# smartswitch.net
KiCad netlist of a schematic drawn in EAGLE
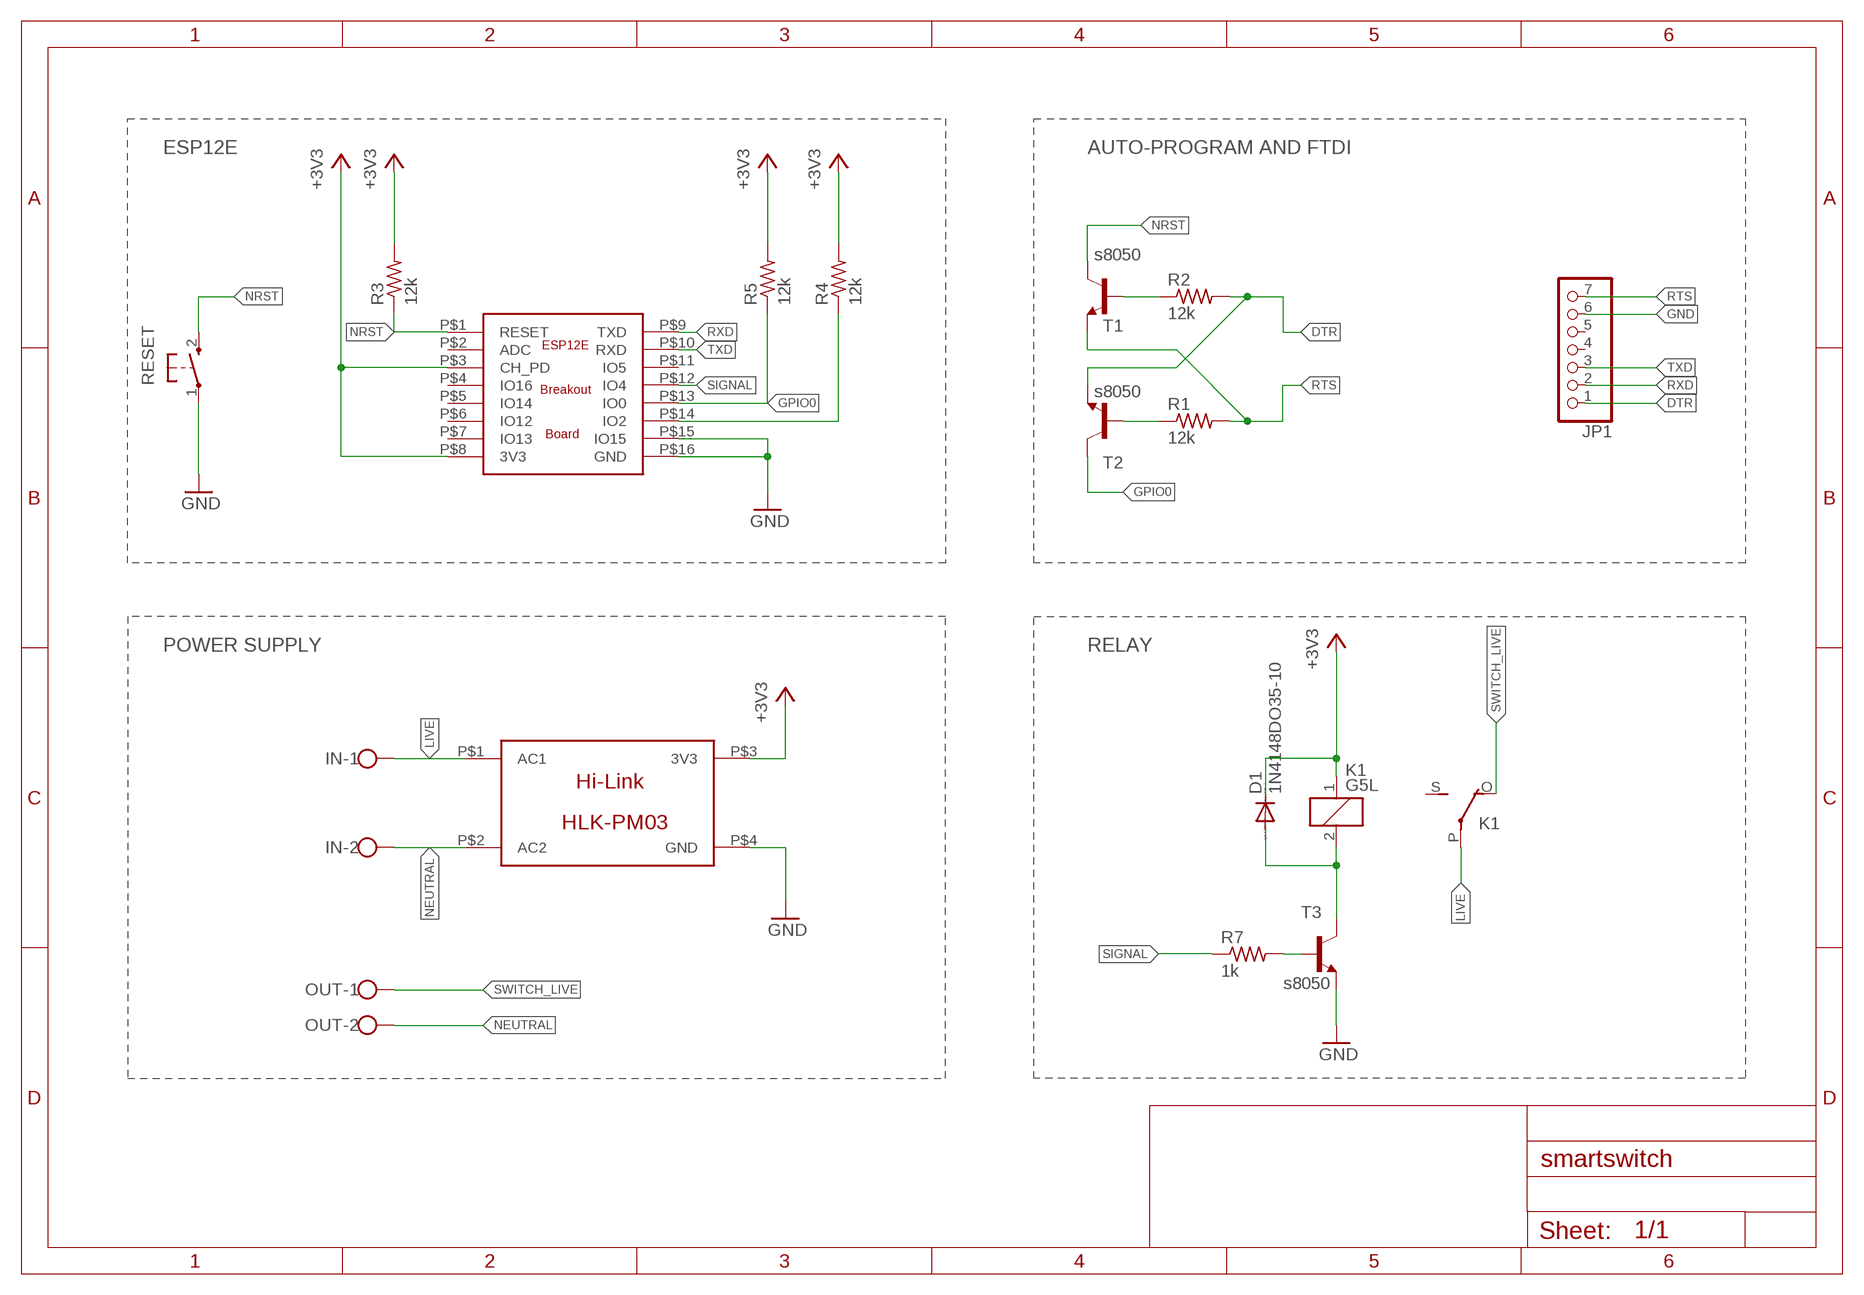
[diagram p0: schematic, sheet 1]

(export (version "E")
  (design (tool "Eeschema 10.0.6"))
  (components
    (comp (ref "D1")
      (value "1N4148DO35-10")
      (footprint "eagle-import:DO35-10")
      (libsource (lib "eagle-import") (part "1N4148DO35-10"))
    )
    (comp (ref "IN")
      (value "W237-102")
      (footprint "eagle-import:W237-102")
      (fields (field (name "MPN") "237-102"))
      (libsource (lib "eagle-import") (part "W237-102"))
    )
    (comp (ref "JP1")
      (value "PINHD-1X7")
      (footprint "eagle-import:1X07")
      (libsource (lib "eagle-import") (part "PINHD-1X7"))
    )
    (comp (ref "K1")
      (value "G5L")
      (footprint "eagle-import:G5LE")
      (libsource (lib "eagle-import") (part "G5L"))
    )
    (comp (ref "OUT")
      (value "W237-102")
      (footprint "eagle-import:W237-102")
      (fields (field (name "MPN") "237-102"))
      (libsource (lib "eagle-import") (part "W237-102"))
    )
    (comp (ref "R1")
      (value "12k")
      (footprint "eagle-import:0309_12")
      (libsource (lib "eagle-import") (part "R-US_0309/12"))
    )
    (comp (ref "R2")
      (value "12k")
      (footprint "eagle-import:0309_12")
      (libsource (lib "eagle-import") (part "R-US_0309/12"))
    )
    (comp (ref "R3")
      (value "12k")
      (footprint "eagle-import:0309_12")
      (libsource (lib "eagle-import") (part "R-US_0309/12"))
    )
    (comp (ref "R4")
      (value "12k")
      (footprint "eagle-import:0309_12")
      (libsource (lib "eagle-import") (part "R-US_0309/12"))
    )
    (comp (ref "R5")
      (value "12k")
      (footprint "eagle-import:0309_12")
      (libsource (lib "eagle-import") (part "R-US_0309/12"))
    )
    (comp (ref "R7")
      (value "1k")
      (footprint "eagle-import:0309_12")
      (libsource (lib "eagle-import") (part "R-US_0309/12"))
    )
    (comp (ref "RESET")
      (value "PB")
      (footprint "eagle-import:PBTH")
      (libsource (lib "eagle-import") (part "PB"))
    )
    (comp (ref "T1")
      (value "s8050")
      (footprint "eagle-import:TO92-EBC")
      (libsource (lib "eagle-import") (part "-NPN-TO92-EBC"))
    )
    (comp (ref "T2")
      (value "s8050")
      (footprint "eagle-import:TO92-EBC")
      (libsource (lib "eagle-import") (part "-NPN-TO92-EBC"))
    )
    (comp (ref "T3")
      (value "s8050")
      (footprint "eagle-import:TO92-EBC")
      (libsource (lib "eagle-import") (part "-NPN-TO92-EBC"))
    )
    (comp (ref "U$1")
      (value "ESP12E_BREAKOUT")
      (footprint "eagle-import:ESP12E")
      (libsource (lib "eagle-import") (part "ESP12E_BREAKOUT"))
    )
    (comp (ref "U$2")
      (value "HLK-PM03")
      (footprint "eagle-import:HLK-PM03")
      (libsource (lib "eagle-import") (part "HLK-PM03"))
    )
  )
  (nets
    (net (code "1") (name "+3V3") (class "Default")
      (node (ref "D1") (pin "C") (pinfunction "C_C") (pintype "passive"))
      (node (ref "K1") (pin "1") (pinfunction "1_1") (pintype "passive"))
      (node (ref "R3") (pin "2") (pinfunction "2_2") (pintype "passive"))
      (node (ref "R4") (pin "2") (pinfunction "2_2") (pintype "passive"))
      (node (ref "R5") (pin "2") (pinfunction "2_2") (pintype "passive"))
      (node (ref "U$1") (pin "P$3") (pinfunction "CH_PD_P$3") (pintype "bidirectional"))
      (node (ref "U$1") (pin "P$8") (pinfunction "3V3_P$8") (pintype "bidirectional"))
      (node (ref "U$2") (pin "P$3") (pinfunction "3V3_P$3") (pintype "bidirectional"))
    )
    (net (code "2") (name "DTR") (class "Default")
      (node (ref "JP1") (pin "1") (pinfunction "1_1") (pintype "passive"))
      (node (ref "R2") (pin "2") (pinfunction "2_2") (pintype "passive"))
      (node (ref "T2") (pin "E") (pinfunction "E_E") (pintype "passive"))
    )
    (net (code "3") (name "GND") (class "Default")
      (node (ref "JP1") (pin "6") (pinfunction "6_6") (pintype "passive"))
      (node (ref "RESET") (pin "1") (pinfunction "P_1") (pintype "passive"))
      (node (ref "T3") (pin "E") (pinfunction "E_E") (pintype "passive"))
      (node (ref "U$1") (pin "P$15") (pinfunction "IO15_P$15") (pintype "bidirectional"))
      (node (ref "U$1") (pin "P$16") (pinfunction "GND_P$16") (pintype "bidirectional"))
      (node (ref "U$2") (pin "P$4") (pinfunction "GND_P$4") (pintype "bidirectional"))
    )
    (net (code "4") (name "GPIO0") (class "Default")
      (node (ref "R5") (pin "1") (pinfunction "1_1") (pintype "passive"))
      (node (ref "T2") (pin "C") (pinfunction "C_C") (pintype "passive"))
      (node (ref "U$1") (pin "P$13") (pinfunction "IO0_P$13") (pintype "bidirectional"))
    )
    (net (code "5") (name "LIVE") (class "Default")
      (node (ref "IN") (pin "1") (pinfunction "KL_1") (pintype "passive"))
      (node (ref "K1") (pin "P") (pinfunction "P_P") (pintype "passive"))
      (node (ref "U$2") (pin "P$1") (pinfunction "AC1_P$1") (pintype "bidirectional"))
    )
    (net (code "6") (name "NEUTRAL") (class "Default")
      (node (ref "IN") (pin "2") (pinfunction "KL_2") (pintype "passive"))
      (node (ref "OUT") (pin "2") (pinfunction "KL_2") (pintype "passive"))
      (node (ref "U$2") (pin "P$2") (pinfunction "AC2_P$2") (pintype "bidirectional"))
    )
    (net (code "7") (name "NRST") (class "Default")
      (node (ref "R3") (pin "1") (pinfunction "1_1") (pintype "passive"))
      (node (ref "RESET") (pin "2") (pinfunction "S_2") (pintype "passive"))
      (node (ref "T1") (pin "C") (pinfunction "C_C") (pintype "passive"))
      (node (ref "U$1") (pin "P$1") (pinfunction "RESET_P$1") (pintype "bidirectional"))
    )
    (net (code "8") (name "Net-(D1-PadA)") (class "Default")
      (node (ref "D1") (pin "A") (pinfunction "A_A") (pintype "passive"))
      (node (ref "K1") (pin "2") (pinfunction "2_2") (pintype "passive"))
      (node (ref "T3") (pin "C") (pinfunction "C_C") (pintype "passive"))
    )
    (net (code "9") (name "Net-(R1-Pad1)") (class "Default")
      (node (ref "R1") (pin "1") (pinfunction "1_1") (pintype "passive"))
      (node (ref "T2") (pin "B") (pinfunction "B_B") (pintype "passive"))
    )
    (net (code "10") (name "Net-(R2-Pad1)") (class "Default")
      (node (ref "R2") (pin "1") (pinfunction "1_1") (pintype "passive"))
      (node (ref "T1") (pin "B") (pinfunction "B_B") (pintype "passive"))
    )
    (net (code "11") (name "Net-(R7-Pad2)") (class "Default")
      (node (ref "R7") (pin "2") (pinfunction "2_2") (pintype "passive"))
      (node (ref "T3") (pin "B") (pinfunction "B_B") (pintype "passive"))
    )
    (net (code "12") (name "Net-(U$1-IO2)") (class "Default")
      (node (ref "R4") (pin "1") (pinfunction "1_1") (pintype "passive"))
      (node (ref "U$1") (pin "P$14") (pinfunction "IO2_P$14") (pintype "bidirectional"))
    )
    (net (code "13") (name "RTS") (class "Default")
      (node (ref "JP1") (pin "7") (pinfunction "7_7") (pintype "passive"))
      (node (ref "R1") (pin "2") (pinfunction "2_2") (pintype "passive"))
      (node (ref "T1") (pin "E") (pinfunction "E_E") (pintype "passive"))
    )
    (net (code "14") (name "RXD") (class "Default")
      (node (ref "JP1") (pin "2") (pinfunction "2_2") (pintype "passive"))
      (node (ref "U$1") (pin "P$9") (pinfunction "TXD_P$9") (pintype "bidirectional"))
    )
    (net (code "15") (name "SIGNAL") (class "Default")
      (node (ref "R7") (pin "1") (pinfunction "1_1") (pintype "passive"))
      (node (ref "U$1") (pin "P$12") (pinfunction "IO4_P$12") (pintype "bidirectional"))
    )
    (net (code "16") (name "SWITCH_LIVE") (class "Default")
      (node (ref "K1") (pin "O") (pinfunction "O_O") (pintype "passive"))
      (node (ref "OUT") (pin "1") (pinfunction "KL_1") (pintype "passive"))
    )
    (net (code "17") (name "TXD") (class "Default")
      (node (ref "JP1") (pin "3") (pinfunction "3_3") (pintype "passive"))
      (node (ref "U$1") (pin "P$10") (pinfunction "RXD_P$10") (pintype "bidirectional"))
    )
    (net (code "18") (name "unconnected-(JP1-Pad4)") (class "Default")
      (node (ref "JP1") (pin "4") (pinfunction "4_4") (pintype "passive"))
    )
    (net (code "19") (name "unconnected-(JP1-Pad5)") (class "Default")
      (node (ref "JP1") (pin "5") (pinfunction "5_5") (pintype "passive"))
    )
    (net (code "20") (name "unconnected-(K1-PadS)") (class "Default")
      (node (ref "K1") (pin "S") (pinfunction "S_S") (pintype "passive"))
    )
    (net (code "21") (name "unconnected-(U$1-ADC-PadP$2)") (class "Default")
      (node (ref "U$1") (pin "P$2") (pinfunction "ADC_P$2") (pintype "bidirectional"))
    )
    (net (code "22") (name "unconnected-(U$1-IO5-PadP$11)") (class "Default")
      (node (ref "U$1") (pin "P$11") (pinfunction "IO5_P$11") (pintype "bidirectional"))
    )
    (net (code "23") (name "unconnected-(U$1-IO12-PadP$6)") (class "Default")
      (node (ref "U$1") (pin "P$6") (pinfunction "IO12_P$6") (pintype "bidirectional"))
    )
    (net (code "24") (name "unconnected-(U$1-IO13-PadP$7)") (class "Default")
      (node (ref "U$1") (pin "P$7") (pinfunction "IO13_P$7") (pintype "bidirectional"))
    )
    (net (code "25") (name "unconnected-(U$1-IO14-PadP$5)") (class "Default")
      (node (ref "U$1") (pin "P$5") (pinfunction "IO14_P$5") (pintype "bidirectional"))
    )
    (net (code "26") (name "unconnected-(U$1-IO16-PadP$4)") (class "Default")
      (node (ref "U$1") (pin "P$4") (pinfunction "IO16_P$4") (pintype "bidirectional"))
    )
  )
)
